# ECU_Adapter.net
KiCad netlist of a schematic drawn in EAGLE
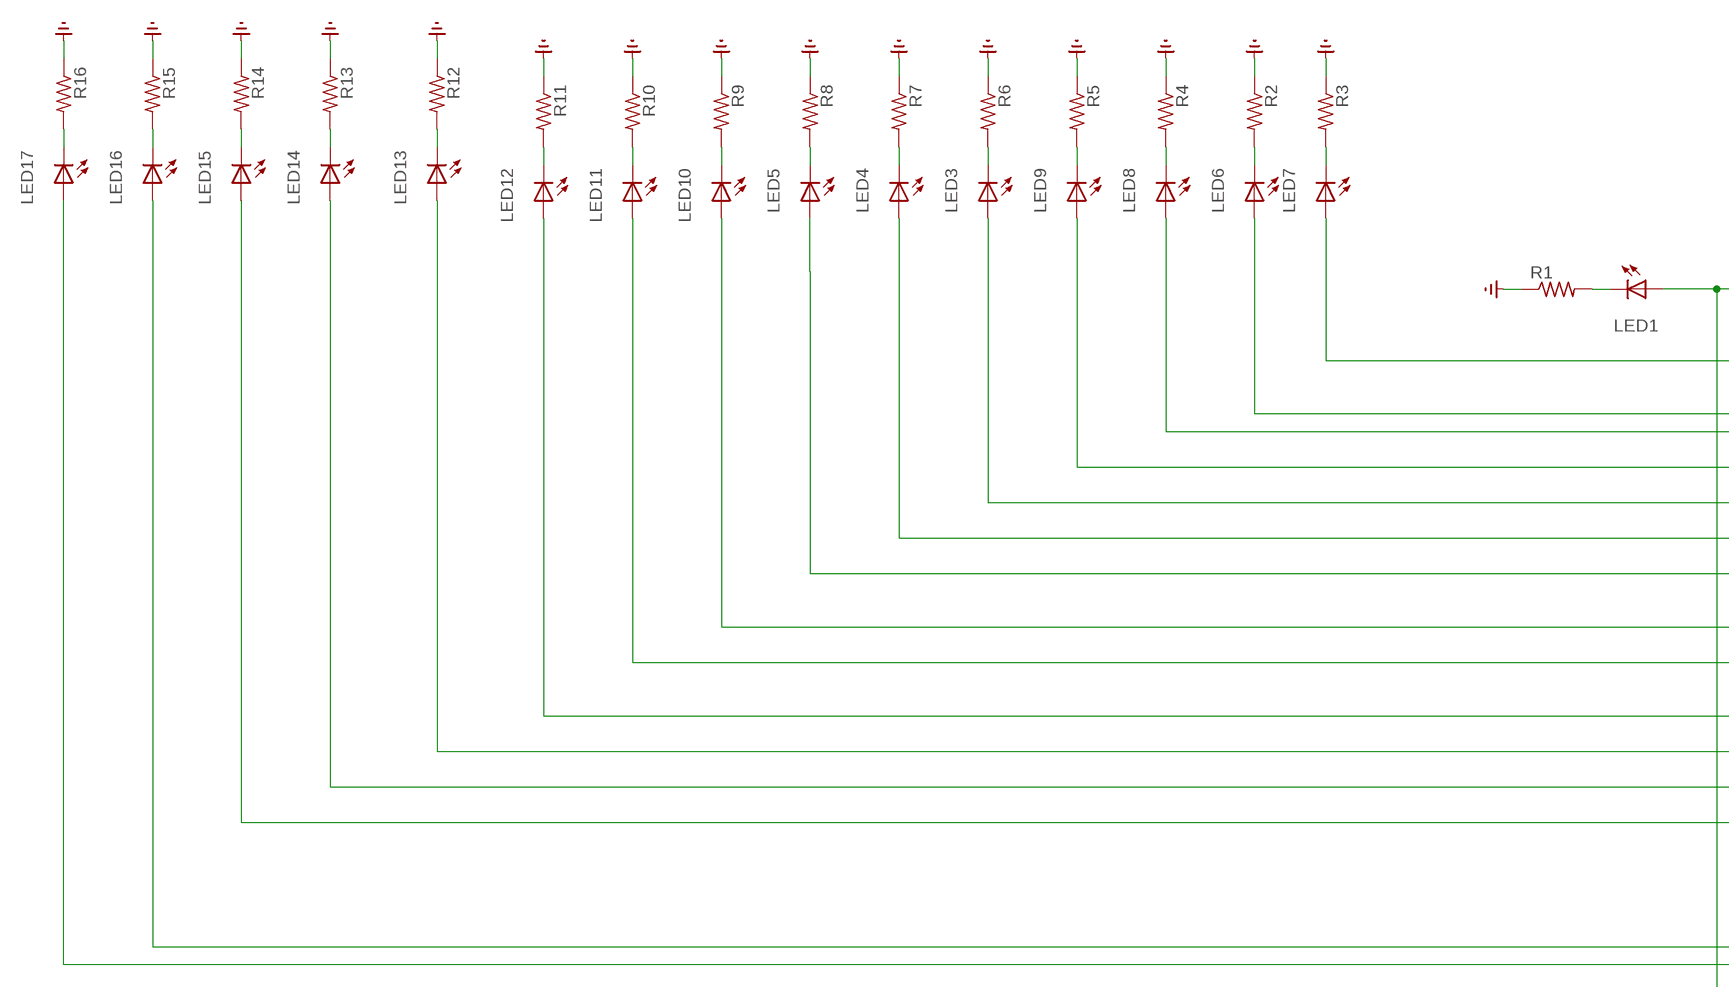
[diagram p0: schematic, sheet 1, part 1 of 2]
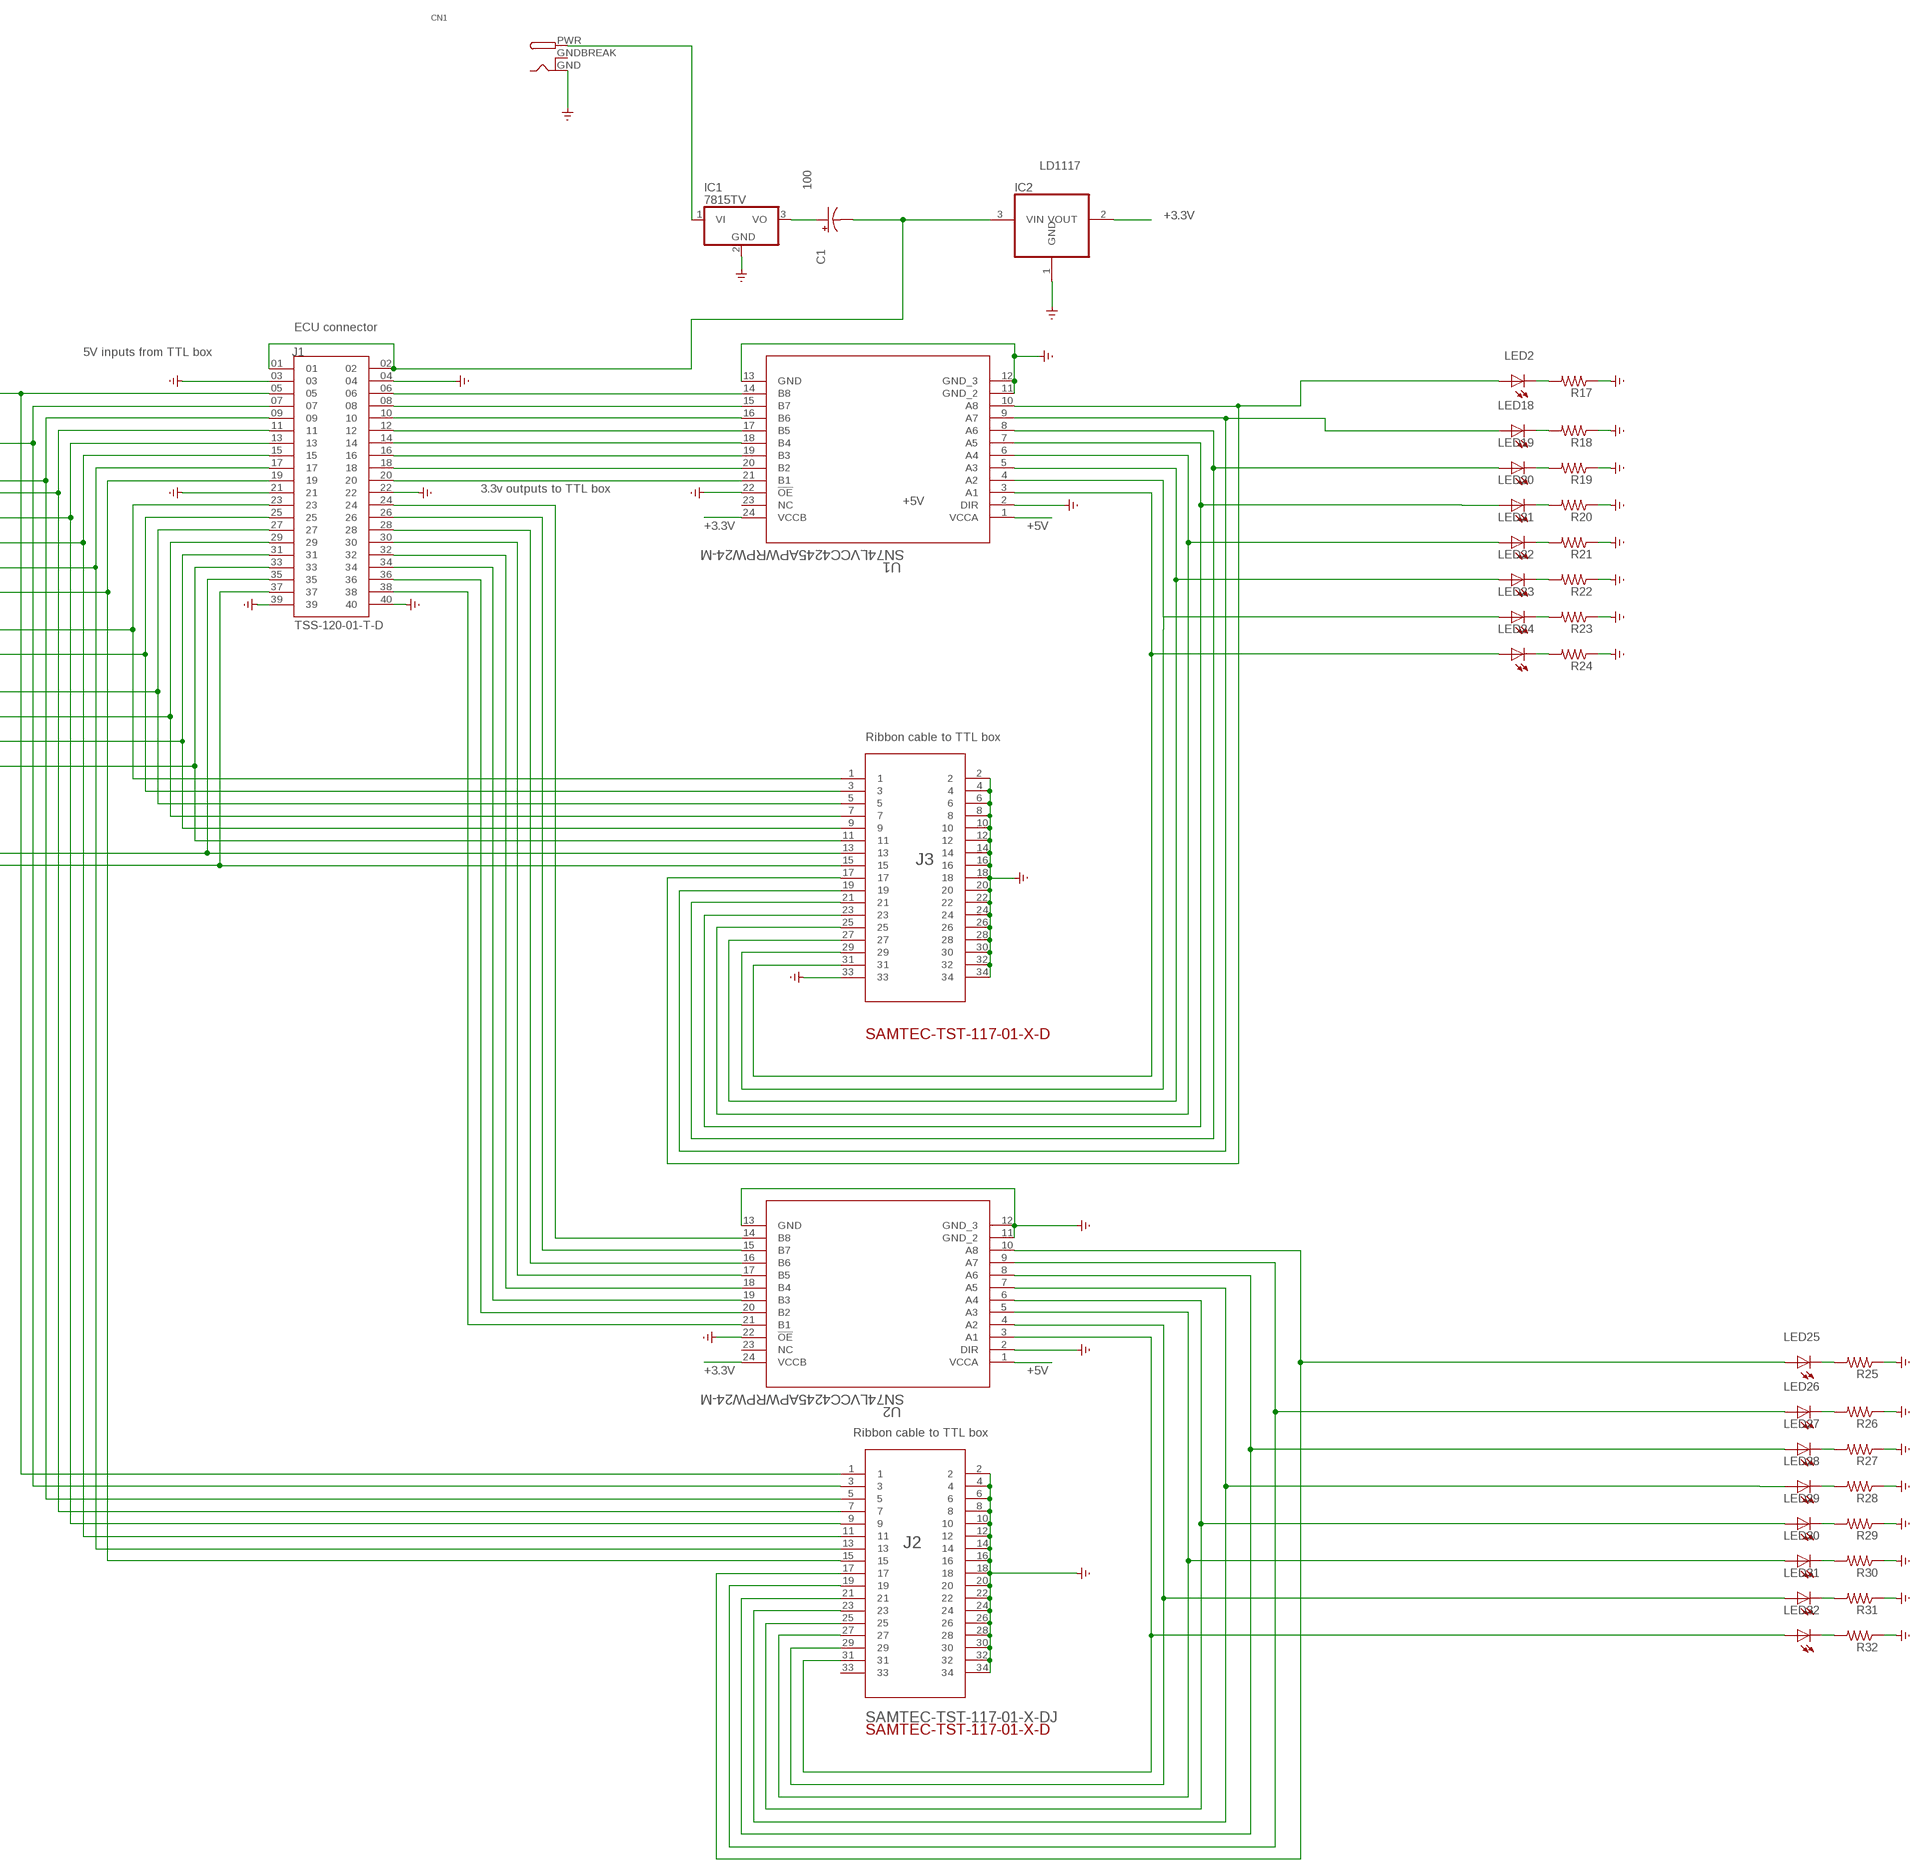
[diagram p1: schematic, sheet 1, part 2 of 2]

(export (version "E")
  (design (tool "Eeschema 10.0.6"))
  (components
    (comp (ref "C1")
      (value "100")
      (footprint "eagle-import:E3,5-10")
      (libsource (lib "eagle-import") (part "CPOL-USE3.5-10"))
    )
    (comp (ref "CN1")
      (value "DCBARRELPTH")
      (footprint "eagle-import:DCJACK_2MM_PTH")
      (libsource (lib "eagle-import") (part "DCBARRELPTH"))
    )
    (comp (ref "IC1")
      (value "7815TV")
      (footprint "eagle-import:TO220V")
      (libsource (lib "eagle-import") (part "78TV15"))
    )
    (comp (ref "IC2")
      (value "LD1117")
      (footprint "eagle-import:SOT223")
      (fields (field (name "MF") "TEXAS INSTRUMENTS") (field (name "MPN") "REG1117FAKTTT"))
      (libsource (lib "eagle-import") (part "LD1117"))
    )
    (comp (ref "J1")
      (value "TSS-120-01-T-D")
      (footprint "eagle-import:SAMTEC_TSS-120-01-T-D")
      (fields (field (name "MF") "Samtec"))
      (libsource (lib "eagle-import") (part "TSS-120-01-T-D"))
    )
    (comp (ref "J2")
      (value "SAMTEC-TST-117-01-X-DJ")
      (footprint "eagle-import:SAMTEC-TST-117-01-X-D")
      (fields
        (field (name "DIGI-KEY_PART_NUMBER") "TST-117-01-L-D-LL-ND")
        (field (name "MF") "Samtec Inc.")
        (field (name "MP") "TST-117-01-L-D")
      )
      (libsource (lib "eagle-import") (part "SAMTEC-TST-117-01-X-DJ"))
    )
    (comp (ref "J3")
      (value "SAMTEC-TST-117-01-X-DJ")
      (footprint "eagle-import:SAMTEC-TST-117-01-X-D")
      (fields
        (field (name "DIGI-KEY_PART_NUMBER") "TST-117-01-L-D-LL-ND")
        (field (name "MF") "Samtec Inc.")
        (field (name "MP") "TST-117-01-L-D")
      )
      (libsource (lib "eagle-import") (part "SAMTEC-TST-117-01-X-DJ"))
    )
    (comp (ref "LED1")
      (value "LEDCHIPLED_0603")
      (footprint "eagle-import:CHIPLED_0603")
      (libsource (lib "eagle-import") (part "LEDCHIPLED_0603"))
    )
    (comp (ref "LED2")
      (value "LEDCHIPLED_0603")
      (footprint "eagle-import:CHIPLED_0603")
      (libsource (lib "eagle-import") (part "LEDCHIPLED_0603"))
    )
    (comp (ref "LED3")
      (value "LEDCHIPLED_0603")
      (footprint "eagle-import:CHIPLED_0603")
      (libsource (lib "eagle-import") (part "LEDCHIPLED_0603"))
    )
    (comp (ref "LED4")
      (value "LEDCHIPLED_0603")
      (footprint "eagle-import:CHIPLED_0603")
      (libsource (lib "eagle-import") (part "LEDCHIPLED_0603"))
    )
    (comp (ref "LED5")
      (value "LEDCHIPLED_0603")
      (footprint "eagle-import:CHIPLED_0603")
      (libsource (lib "eagle-import") (part "LEDCHIPLED_0603"))
    )
    (comp (ref "LED6")
      (value "LEDCHIPLED_0603")
      (footprint "eagle-import:CHIPLED_0603")
      (libsource (lib "eagle-import") (part "LEDCHIPLED_0603"))
    )
    (comp (ref "LED7")
      (value "LEDCHIPLED_0603")
      (footprint "eagle-import:CHIPLED_0603")
      (libsource (lib "eagle-import") (part "LEDCHIPLED_0603"))
    )
    (comp (ref "LED8")
      (value "LEDCHIPLED_0603")
      (footprint "eagle-import:CHIPLED_0603")
      (libsource (lib "eagle-import") (part "LEDCHIPLED_0603"))
    )
    (comp (ref "LED9")
      (value "LEDCHIPLED_0603")
      (footprint "eagle-import:CHIPLED_0603")
      (libsource (lib "eagle-import") (part "LEDCHIPLED_0603"))
    )
    (comp (ref "LED10")
      (value "LEDCHIPLED_0603")
      (footprint "eagle-import:CHIPLED_0603")
      (libsource (lib "eagle-import") (part "LEDCHIPLED_0603"))
    )
    (comp (ref "LED11")
      (value "LEDCHIPLED_0603")
      (footprint "eagle-import:CHIPLED_0603")
      (libsource (lib "eagle-import") (part "LEDCHIPLED_0603"))
    )
    (comp (ref "LED12")
      (value "LEDCHIPLED_0603")
      (footprint "eagle-import:CHIPLED_0603")
      (libsource (lib "eagle-import") (part "LEDCHIPLED_0603"))
    )
    (comp (ref "LED13")
      (value "LEDCHIPLED_0603")
      (footprint "eagle-import:CHIPLED_0603")
      (libsource (lib "eagle-import") (part "LEDCHIPLED_0603"))
    )
    (comp (ref "LED14")
      (value "LEDCHIPLED_0603")
      (footprint "eagle-import:CHIPLED_0603")
      (libsource (lib "eagle-import") (part "LEDCHIPLED_0603"))
    )
    (comp (ref "LED15")
      (value "LEDCHIPLED_0603")
      (footprint "eagle-import:CHIPLED_0603")
      (libsource (lib "eagle-import") (part "LEDCHIPLED_0603"))
    )
    (comp (ref "LED16")
      (value "LEDCHIPLED_0603")
      (footprint "eagle-import:CHIPLED_0603")
      (libsource (lib "eagle-import") (part "LEDCHIPLED_0603"))
    )
    (comp (ref "LED17")
      (value "LEDCHIPLED_0603")
      (footprint "eagle-import:CHIPLED_0603")
      (libsource (lib "eagle-import") (part "LEDCHIPLED_0603"))
    )
    (comp (ref "LED18")
      (value "LEDCHIPLED_0603")
      (footprint "eagle-import:CHIPLED_0603")
      (libsource (lib "eagle-import") (part "LEDCHIPLED_0603"))
    )
    (comp (ref "LED19")
      (value "LEDCHIPLED_0603")
      (footprint "eagle-import:CHIPLED_0603")
      (libsource (lib "eagle-import") (part "LEDCHIPLED_0603"))
    )
    (comp (ref "LED20")
      (value "LEDCHIPLED_0603")
      (footprint "eagle-import:CHIPLED_0603")
      (libsource (lib "eagle-import") (part "LEDCHIPLED_0603"))
    )
    (comp (ref "LED21")
      (value "LEDCHIPLED_0603")
      (footprint "eagle-import:CHIPLED_0603")
      (libsource (lib "eagle-import") (part "LEDCHIPLED_0603"))
    )
    (comp (ref "LED22")
      (value "LEDCHIPLED_0603")
      (footprint "eagle-import:CHIPLED_0603")
      (libsource (lib "eagle-import") (part "LEDCHIPLED_0603"))
    )
    (comp (ref "LED23")
      (value "LEDCHIPLED_0603")
      (footprint "eagle-import:CHIPLED_0603")
      (libsource (lib "eagle-import") (part "LEDCHIPLED_0603"))
    )
    (comp (ref "LED24")
      (value "LEDCHIPLED_0603")
      (footprint "eagle-import:CHIPLED_0603")
      (libsource (lib "eagle-import") (part "LEDCHIPLED_0603"))
    )
    (comp (ref "LED25")
      (value "LEDCHIPLED_0603")
      (footprint "eagle-import:CHIPLED_0603")
      (libsource (lib "eagle-import") (part "LEDCHIPLED_0603"))
    )
    (comp (ref "LED26")
      (value "LEDCHIPLED_0603")
      (footprint "eagle-import:CHIPLED_0603")
      (libsource (lib "eagle-import") (part "LEDCHIPLED_0603"))
    )
    (comp (ref "LED27")
      (value "LEDCHIPLED_0603")
      (footprint "eagle-import:CHIPLED_0603")
      (libsource (lib "eagle-import") (part "LEDCHIPLED_0603"))
    )
    (comp (ref "LED28")
      (value "LEDCHIPLED_0603")
      (footprint "eagle-import:CHIPLED_0603")
      (libsource (lib "eagle-import") (part "LEDCHIPLED_0603"))
    )
    (comp (ref "LED29")
      (value "LEDCHIPLED_0603")
      (footprint "eagle-import:CHIPLED_0603")
      (libsource (lib "eagle-import") (part "LEDCHIPLED_0603"))
    )
    (comp (ref "LED30")
      (value "LEDCHIPLED_0603")
      (footprint "eagle-import:CHIPLED_0603")
      (libsource (lib "eagle-import") (part "LEDCHIPLED_0603"))
    )
    (comp (ref "LED31")
      (value "LEDCHIPLED_0603")
      (footprint "eagle-import:CHIPLED_0603")
      (libsource (lib "eagle-import") (part "LEDCHIPLED_0603"))
    )
    (comp (ref "LED32")
      (value "LEDCHIPLED_0603")
      (footprint "eagle-import:CHIPLED_0603")
      (libsource (lib "eagle-import") (part "LEDCHIPLED_0603"))
    )
    (comp (ref "R1")
      (value "R-US_R0603")
      (footprint "eagle-import:R0603")
      (libsource (lib "eagle-import") (part "R-US_R0603"))
    )
    (comp (ref "R2")
      (value "R-US_R0603")
      (footprint "eagle-import:R0603")
      (libsource (lib "eagle-import") (part "R-US_R0603"))
    )
    (comp (ref "R3")
      (value "R-US_R0603")
      (footprint "eagle-import:R0603")
      (libsource (lib "eagle-import") (part "R-US_R0603"))
    )
    (comp (ref "R4")
      (value "R-US_R0603")
      (footprint "eagle-import:R0603")
      (libsource (lib "eagle-import") (part "R-US_R0603"))
    )
    (comp (ref "R5")
      (value "R-US_R0603")
      (footprint "eagle-import:R0603")
      (libsource (lib "eagle-import") (part "R-US_R0603"))
    )
    (comp (ref "R6")
      (value "R-US_R0603")
      (footprint "eagle-import:R0603")
      (libsource (lib "eagle-import") (part "R-US_R0603"))
    )
    (comp (ref "R7")
      (value "R-US_R0603")
      (footprint "eagle-import:R0603")
      (libsource (lib "eagle-import") (part "R-US_R0603"))
    )
    (comp (ref "R8")
      (value "R-US_R0603")
      (footprint "eagle-import:R0603")
      (libsource (lib "eagle-import") (part "R-US_R0603"))
    )
    (comp (ref "R9")
      (value "R-US_R0603")
      (footprint "eagle-import:R0603")
      (libsource (lib "eagle-import") (part "R-US_R0603"))
    )
    (comp (ref "R10")
      (value "R-US_R0603")
      (footprint "eagle-import:R0603")
      (libsource (lib "eagle-import") (part "R-US_R0603"))
    )
    (comp (ref "R11")
      (value "R-US_R0603")
      (footprint "eagle-import:R0603")
      (libsource (lib "eagle-import") (part "R-US_R0603"))
    )
    (comp (ref "R12")
      (value "R-US_R0603")
      (footprint "eagle-import:R0603")
      (libsource (lib "eagle-import") (part "R-US_R0603"))
    )
    (comp (ref "R13")
      (value "R-US_R0603")
      (footprint "eagle-import:R0603")
      (libsource (lib "eagle-import") (part "R-US_R0603"))
    )
    (comp (ref "R14")
      (value "R-US_R0603")
      (footprint "eagle-import:R0603")
      (libsource (lib "eagle-import") (part "R-US_R0603"))
    )
    (comp (ref "R15")
      (value "R-US_R0603")
      (footprint "eagle-import:R0603")
      (libsource (lib "eagle-import") (part "R-US_R0603"))
    )
    (comp (ref "R16")
      (value "R-US_R0603")
      (footprint "eagle-import:R0603")
      (libsource (lib "eagle-import") (part "R-US_R0603"))
    )
    (comp (ref "R17")
      (value "R-US_R0603")
      (footprint "eagle-import:R0603")
      (libsource (lib "eagle-import") (part "R-US_R0603"))
    )
    (comp (ref "R18")
      (value "R-US_R0603")
      (footprint "eagle-import:R0603")
      (libsource (lib "eagle-import") (part "R-US_R0603"))
    )
    (comp (ref "R19")
      (value "R-US_R0603")
      (footprint "eagle-import:R0603")
      (libsource (lib "eagle-import") (part "R-US_R0603"))
    )
    (comp (ref "R20")
      (value "R-US_R0603")
      (footprint "eagle-import:R0603")
      (libsource (lib "eagle-import") (part "R-US_R0603"))
    )
    (comp (ref "R21")
      (value "R-US_R0603")
      (footprint "eagle-import:R0603")
      (libsource (lib "eagle-import") (part "R-US_R0603"))
    )
    (comp (ref "R22")
      (value "R-US_R0603")
      (footprint "eagle-import:R0603")
      (libsource (lib "eagle-import") (part "R-US_R0603"))
    )
    (comp (ref "R23")
      (value "R-US_R0603")
      (footprint "eagle-import:R0603")
      (libsource (lib "eagle-import") (part "R-US_R0603"))
    )
    (comp (ref "R24")
      (value "R-US_R0603")
      (footprint "eagle-import:R0603")
      (libsource (lib "eagle-import") (part "R-US_R0603"))
    )
    (comp (ref "R25")
      (value "R-US_R0603")
      (footprint "eagle-import:R0603")
      (libsource (lib "eagle-import") (part "R-US_R0603"))
    )
    (comp (ref "R26")
      (value "R-US_R0603")
      (footprint "eagle-import:R0603")
      (libsource (lib "eagle-import") (part "R-US_R0603"))
    )
    (comp (ref "R27")
      (value "R-US_R0603")
      (footprint "eagle-import:R0603")
      (libsource (lib "eagle-import") (part "R-US_R0603"))
    )
    (comp (ref "R28")
      (value "R-US_R0603")
      (footprint "eagle-import:R0603")
      (libsource (lib "eagle-import") (part "R-US_R0603"))
    )
    (comp (ref "R29")
      (value "R-US_R0603")
      (footprint "eagle-import:R0603")
      (libsource (lib "eagle-import") (part "R-US_R0603"))
    )
    (comp (ref "R30")
      (value "R-US_R0603")
      (footprint "eagle-import:R0603")
      (libsource (lib "eagle-import") (part "R-US_R0603"))
    )
    (comp (ref "R31")
      (value "R-US_R0603")
      (footprint "eagle-import:R0603")
      (libsource (lib "eagle-import") (part "R-US_R0603"))
    )
    (comp (ref "R32")
      (value "R-US_R0603")
      (footprint "eagle-import:R0603")
      (libsource (lib "eagle-import") (part "R-US_R0603"))
    )
    (comp (ref "U1")
      (value "SN74LVCC4245APWRPW24-M")
      (footprint "eagle-import:PW24-M")
      (fields
        (field (name "GENERIC_PART_NUMBER") "SN74LVCC4245A")
        (field (name "MANUFACTURER") "Texas Instruments")
        (field (name "MANUFACTURER_PART_NUMBER") "SN74LVCC4245APWR")
      )
      (libsource (lib "eagle-import") (part "SN74LVCC4245APWRPW24-M"))
    )
    (comp (ref "U2")
      (value "SN74LVCC4245APWRPW24-M")
      (footprint "eagle-import:PW24-M")
      (fields
        (field (name "GENERIC_PART_NUMBER") "SN74LVCC4245A")
        (field (name "MANUFACTURER") "Texas Instruments")
        (field (name "MANUFACTURER_PART_NUMBER") "SN74LVCC4245APWR")
      )
      (libsource (lib "eagle-import") (part "SN74LVCC4245APWRPW24-M"))
    )
  )
  (nets
    (net (code "1") (name "/+3.3V") (class "Default")
      (node (ref "IC2") (pin "2") (pinfunction "VOUT_2") (pintype "output"))
      (node (ref "U1") (pin "24") (pinfunction "VCCB_24") (pintype "power_in"))
      (node (ref "U2") (pin "24") (pinfunction "VCCB_24") (pintype "power_in"))
    )
    (net (code "2") (name "/+5V") (class "Default")
      (node (ref "C1") (pin "-") (pinfunction "-_-") (pintype "passive"))
      (node (ref "IC2") (pin "3") (pinfunction "VIN_3") (pintype "input"))
      (node (ref "J1") (pin "01") (pinfunction "01_01") (pintype "passive"))
      (node (ref "J1") (pin "02") (pinfunction "02_02") (pintype "passive"))
      (node (ref "U1") (pin "1") (pinfunction "VCCA_1") (pintype "power_in"))
      (node (ref "U2") (pin "1") (pinfunction "VCCA_1") (pintype "power_in"))
    )
    (net (code "3") (name "/GNDBREAK") (class "Default")
      (node (ref "CN1") (pin "GNDBREAK") (pinfunction "GNDBREAK_GNDBREAK") (pintype "power_in"))
    )
    (net (code "4") (name "Net-(IC1-VI)") (class "Default")
      (node (ref "CN1") (pin "PWR") (pinfunction "PWR_PWR") (pintype "power_in"))
      (node (ref "IC1") (pin "1") (pinfunction "VI_1") (pintype "input"))
    )
    (net (code "5") (name "Net-(IC1-VO)") (class "Default")
      (node (ref "C1") (pin "+") (pinfunction "+_+") (pintype "passive"))
      (node (ref "IC1") (pin "3") (pinfunction "VO_3") (pintype "passive"))
    )
    (net (code "6") (name "Net-(J1-Pad05)") (class "Default")
      (node (ref "J1") (pin "05") (pinfunction "05_05") (pintype "passive"))
      (node (ref "J2") (pin "1") (pinfunction "1_1") (pintype "passive"))
      (node (ref "LED1") (pin "A") (pinfunction "A_A") (pintype "passive"))
    )
    (net (code "7") (name "Net-(J1-Pad07)") (class "Default")
      (node (ref "J1") (pin "07") (pinfunction "07_07") (pintype "passive"))
      (node (ref "J2") (pin "3") (pinfunction "3_3") (pintype "passive"))
      (node (ref "LED7") (pin "A") (pinfunction "A_A") (pintype "passive"))
    )
    (net (code "8") (name "Net-(J1-Pad09)") (class "Default")
      (node (ref "J1") (pin "09") (pinfunction "09_09") (pintype "passive"))
      (node (ref "J2") (pin "5") (pinfunction "5_5") (pintype "passive"))
      (node (ref "LED6") (pin "A") (pinfunction "A_A") (pintype "passive"))
    )
    (net (code "9") (name "Net-(J1-Pad11)") (class "Default")
      (node (ref "J1") (pin "11") (pinfunction "11_11") (pintype "passive"))
      (node (ref "J2") (pin "7") (pinfunction "7_7") (pintype "passive"))
      (node (ref "LED8") (pin "A") (pinfunction "A_A") (pintype "passive"))
    )
    (net (code "10") (name "Net-(J1-Pad13)") (class "Default")
      (node (ref "J1") (pin "13") (pinfunction "13_13") (pintype "passive"))
      (node (ref "J2") (pin "9") (pinfunction "9_9") (pintype "passive"))
      (node (ref "LED9") (pin "A") (pinfunction "A_A") (pintype "passive"))
    )
    (net (code "11") (name "Net-(J1-Pad15)") (class "Default")
      (node (ref "J1") (pin "15") (pinfunction "15_15") (pintype "passive"))
      (node (ref "J2") (pin "11") (pinfunction "11_11") (pintype "passive"))
      (node (ref "LED3") (pin "A") (pinfunction "A_A") (pintype "passive"))
    )
    (net (code "12") (name "Net-(J1-Pad17)") (class "Default")
      (node (ref "J1") (pin "17") (pinfunction "17_17") (pintype "passive"))
      (node (ref "J2") (pin "13") (pinfunction "13_13") (pintype "passive"))
      (node (ref "LED4") (pin "A") (pinfunction "A_A") (pintype "passive"))
    )
    (net (code "13") (name "Net-(J1-Pad19)") (class "Default")
      (node (ref "J1") (pin "19") (pinfunction "19_19") (pintype "passive"))
      (node (ref "J2") (pin "15") (pinfunction "15_15") (pintype "passive"))
      (node (ref "LED5") (pin "A") (pinfunction "A_A") (pintype "passive"))
    )
    (net (code "14") (name "Net-(J1-Pad23)") (class "Default")
      (node (ref "J1") (pin "23") (pinfunction "23_23") (pintype "passive"))
      (node (ref "J3") (pin "1") (pinfunction "1_1") (pintype "passive"))
      (node (ref "LED10") (pin "A") (pinfunction "A_A") (pintype "passive"))
    )
    (net (code "15") (name "Net-(J1-Pad25)") (class "Default")
      (node (ref "J1") (pin "25") (pinfunction "25_25") (pintype "passive"))
      (node (ref "J3") (pin "3") (pinfunction "3_3") (pintype "passive"))
      (node (ref "LED11") (pin "A") (pinfunction "A_A") (pintype "passive"))
    )
    (net (code "16") (name "Net-(J1-Pad27)") (class "Default")
      (node (ref "J1") (pin "27") (pinfunction "27_27") (pintype "passive"))
      (node (ref "J3") (pin "5") (pinfunction "5_5") (pintype "passive"))
      (node (ref "LED12") (pin "A") (pinfunction "A_A") (pintype "passive"))
    )
    (net (code "17") (name "Net-(J1-Pad29)") (class "Default")
      (node (ref "J1") (pin "29") (pinfunction "29_29") (pintype "passive"))
      (node (ref "J3") (pin "7") (pinfunction "7_7") (pintype "passive"))
      (node (ref "LED13") (pin "A") (pinfunction "A_A") (pintype "passive"))
    )
    (net (code "18") (name "Net-(J1-Pad31)") (class "Default")
      (node (ref "J1") (pin "31") (pinfunction "31_31") (pintype "passive"))
      (node (ref "J3") (pin "9") (pinfunction "9_9") (pintype "passive"))
      (node (ref "LED14") (pin "A") (pinfunction "A_A") (pintype "passive"))
    )
    (net (code "19") (name "Net-(J1-Pad33)") (class "Default")
      (node (ref "J1") (pin "33") (pinfunction "33_33") (pintype "passive"))
      (node (ref "J3") (pin "11") (pinfunction "11_11") (pintype "passive"))
      (node (ref "LED15") (pin "A") (pinfunction "A_A") (pintype "passive"))
    )
    (net (code "20") (name "Net-(J1-Pad35)") (class "Default")
      (node (ref "J1") (pin "35") (pinfunction "35_35") (pintype "passive"))
      (node (ref "J3") (pin "13") (pinfunction "13_13") (pintype "passive"))
      (node (ref "LED16") (pin "A") (pinfunction "A_A") (pintype "passive"))
    )
    (net (code "21") (name "Net-(J1-Pad37)") (class "Default")
      (node (ref "J1") (pin "37") (pinfunction "37_37") (pintype "passive"))
      (node (ref "J3") (pin "15") (pinfunction "15_15") (pintype "passive"))
      (node (ref "LED17") (pin "A") (pinfunction "A_A") (pintype "passive"))
    )
    (net (code "22") (name "Net-(LED1-PadC)") (class "Default")
      (node (ref "LED1") (pin "C") (pinfunction "C_C") (pintype "passive"))
      (node (ref "R1") (pin "2") (pinfunction "2_2") (pintype "passive"))
    )
    (net (code "23") (name "Net-(LED2-PadC)") (class "Default")
      (node (ref "LED2") (pin "C") (pinfunction "C_C") (pintype "passive"))
      (node (ref "R17") (pin "2") (pinfunction "2_2") (pintype "passive"))
    )
    (net (code "24") (name "Net-(LED3-PadC)") (class "Default")
      (node (ref "LED3") (pin "C") (pinfunction "C_C") (pintype "passive"))
      (node (ref "R6") (pin "2") (pinfunction "2_2") (pintype "passive"))
    )
    (net (code "25") (name "Net-(LED4-PadC)") (class "Default")
      (node (ref "LED4") (pin "C") (pinfunction "C_C") (pintype "passive"))
      (node (ref "R7") (pin "2") (pinfunction "2_2") (pintype "passive"))
    )
    (net (code "26") (name "Net-(LED5-PadC)") (class "Default")
      (node (ref "LED5") (pin "C") (pinfunction "C_C") (pintype "passive"))
      (node (ref "R8") (pin "2") (pinfunction "2_2") (pintype "passive"))
    )
    (net (code "27") (name "Net-(LED6-PadC)") (class "Default")
      (node (ref "LED6") (pin "C") (pinfunction "C_C") (pintype "passive"))
      (node (ref "R2") (pin "2") (pinfunction "2_2") (pintype "passive"))
    )
    (net (code "28") (name "Net-(LED7-PadC)") (class "Default")
      (node (ref "LED7") (pin "C") (pinfunction "C_C") (pintype "passive"))
      (node (ref "R3") (pin "2") (pinfunction "2_2") (pintype "passive"))
    )
    (net (code "29") (name "Net-(LED8-PadC)") (class "Default")
      (node (ref "LED8") (pin "C") (pinfunction "C_C") (pintype "passive"))
      (node (ref "R4") (pin "2") (pinfunction "2_2") (pintype "passive"))
    )
    (net (code "30") (name "Net-(LED9-PadC)") (class "Default")
      (node (ref "LED9") (pin "C") (pinfunction "C_C") (pintype "passive"))
      (node (ref "R5") (pin "2") (pinfunction "2_2") (pintype "passive"))
    )
    (net (code "31") (name "Net-(LED10-PadC)") (class "Default")
      (node (ref "LED10") (pin "C") (pinfunction "C_C") (pintype "passive"))
      (node (ref "R9") (pin "2") (pinfunction "2_2") (pintype "passive"))
    )
    (net (code "32") (name "Net-(LED11-PadC)") (class "Default")
      (node (ref "LED11") (pin "C") (pinfunction "C_C") (pintype "passive"))
      (node (ref "R10") (pin "2") (pinfunction "2_2") (pintype "passive"))
    )
    (net (code "33") (name "Net-(LED12-PadC)") (class "Default")
      (node (ref "LED12") (pin "C") (pinfunction "C_C") (pintype "passive"))
      (node (ref "R11") (pin "2") (pinfunction "2_2") (pintype "passive"))
    )
    (net (code "34") (name "Net-(LED13-PadC)") (class "Default")
      (node (ref "LED13") (pin "C") (pinfunction "C_C") (pintype "passive"))
      (node (ref "R12") (pin "2") (pinfunction "2_2") (pintype "passive"))
    )
    (net (code "35") (name "Net-(LED14-PadC)") (class "Default")
      (node (ref "LED14") (pin "C") (pinfunction "C_C") (pintype "passive"))
      (node (ref "R13") (pin "2") (pinfunction "2_2") (pintype "passive"))
    )
    (net (code "36") (name "Net-(LED15-PadC)") (class "Default")
      (node (ref "LED15") (pin "C") (pinfunction "C_C") (pintype "passive"))
      (node (ref "R14") (pin "2") (pinfunction "2_2") (pintype "passive"))
    )
    (net (code "37") (name "Net-(LED16-PadC)") (class "Default")
      (node (ref "LED16") (pin "C") (pinfunction "C_C") (pintype "passive"))
      (node (ref "R15") (pin "2") (pinfunction "2_2") (pintype "passive"))
    )
    (net (code "38") (name "Net-(LED17-PadC)") (class "Default")
      (node (ref "LED17") (pin "C") (pinfunction "C_C") (pintype "passive"))
      (node (ref "R16") (pin "2") (pinfunction "2_2") (pintype "passive"))
    )
    (net (code "39") (name "Net-(LED18-PadC)") (class "Default")
      (node (ref "LED18") (pin "C") (pinfunction "C_C") (pintype "passive"))
      (node (ref "R18") (pin "2") (pinfunction "2_2") (pintype "passive"))
    )
    (net (code "40") (name "Net-(LED19-PadC)") (class "Default")
      (node (ref "LED19") (pin "C") (pinfunction "C_C") (pintype "passive"))
      (node (ref "R19") (pin "2") (pinfunction "2_2") (pintype "passive"))
    )
    (net (code "41") (name "Net-(LED20-PadC)") (class "Default")
      (node (ref "LED20") (pin "C") (pinfunction "C_C") (pintype "passive"))
      (node (ref "R20") (pin "2") (pinfunction "2_2") (pintype "passive"))
    )
    (net (code "42") (name "Net-(LED21-PadC)") (class "Default")
      (node (ref "LED21") (pin "C") (pinfunction "C_C") (pintype "passive"))
      (node (ref "R21") (pin "2") (pinfunction "2_2") (pintype "passive"))
    )
    (net (code "43") (name "Net-(LED22-PadC)") (class "Default")
      (node (ref "LED22") (pin "C") (pinfunction "C_C") (pintype "passive"))
      (node (ref "R22") (pin "2") (pinfunction "2_2") (pintype "passive"))
    )
    (net (code "44") (name "Net-(LED23-PadC)") (class "Default")
      (node (ref "LED23") (pin "C") (pinfunction "C_C") (pintype "passive"))
      (node (ref "R23") (pin "2") (pinfunction "2_2") (pintype "passive"))
    )
    (net (code "45") (name "Net-(LED24-PadC)") (class "Default")
      (node (ref "LED24") (pin "C") (pinfunction "C_C") (pintype "passive"))
      (node (ref "R24") (pin "2") (pinfunction "2_2") (pintype "passive"))
    )
    (net (code "46") (name "Net-(LED25-PadC)") (class "Default")
      (node (ref "LED25") (pin "C") (pinfunction "C_C") (pintype "passive"))
      (node (ref "R25") (pin "2") (pinfunction "2_2") (pintype "passive"))
    )
    (net (code "47") (name "Net-(LED26-PadC)") (class "Default")
      (node (ref "LED26") (pin "C") (pinfunction "C_C") (pintype "passive"))
      (node (ref "R26") (pin "2") (pinfunction "2_2") (pintype "passive"))
    )
    (net (code "48") (name "Net-(LED27-PadC)") (class "Default")
      (node (ref "LED27") (pin "C") (pinfunction "C_C") (pintype "passive"))
      (node (ref "R27") (pin "2") (pinfunction "2_2") (pintype "passive"))
    )
    (net (code "49") (name "Net-(LED28-PadC)") (class "Default")
      (node (ref "LED28") (pin "C") (pinfunction "C_C") (pintype "passive"))
      (node (ref "R28") (pin "2") (pinfunction "2_2") (pintype "passive"))
    )
    (net (code "50") (name "Net-(LED29-PadC)") (class "Default")
      (node (ref "LED29") (pin "C") (pinfunction "C_C") (pintype "passive"))
      (node (ref "R29") (pin "2") (pinfunction "2_2") (pintype "passive"))
    )
    (net (code "51") (name "Net-(LED30-PadC)") (class "Default")
      (node (ref "LED30") (pin "C") (pinfunction "C_C") (pintype "passive"))
      (node (ref "R30") (pin "2") (pinfunction "2_2") (pintype "passive"))
    )
    (net (code "52") (name "Net-(LED31-PadC)") (class "Default")
      (node (ref "LED31") (pin "C") (pinfunction "C_C") (pintype "passive"))
      (node (ref "R31") (pin "2") (pinfunction "2_2") (pintype "passive"))
    )
    (net (code "53") (name "Net-(LED32-PadC)") (class "Default")
      (node (ref "LED32") (pin "C") (pinfunction "C_C") (pintype "passive"))
      (node (ref "R32") (pin "2") (pinfunction "2_2") (pintype "passive"))
    )
    (net (code "54") (name "Net-(U1-A1)") (class "Default")
      (node (ref "J3") (pin "31") (pinfunction "31_31") (pintype "passive"))
      (node (ref "LED24") (pin "A") (pinfunction "A_A") (pintype "passive"))
      (node (ref "U1") (pin "3") (pinfunction "A1_3") (pintype "bidirectional"))
    )
    (net (code "55") (name "Net-(U1-A2)") (class "Default")
      (node (ref "J3") (pin "29") (pinfunction "29_29") (pintype "passive"))
      (node (ref "LED23") (pin "A") (pinfunction "A_A") (pintype "passive"))
      (node (ref "U1") (pin "4") (pinfunction "A2_4") (pintype "bidirectional"))
    )
    (net (code "56") (name "Net-(U1-A3)") (class "Default")
      (node (ref "J3") (pin "27") (pinfunction "27_27") (pintype "passive"))
      (node (ref "LED22") (pin "A") (pinfunction "A_A") (pintype "passive"))
      (node (ref "U1") (pin "5") (pinfunction "A3_5") (pintype "bidirectional"))
    )
    (net (code "57") (name "Net-(U1-A4)") (class "Default")
      (node (ref "J3") (pin "25") (pinfunction "25_25") (pintype "passive"))
      (node (ref "LED21") (pin "A") (pinfunction "A_A") (pintype "passive"))
      (node (ref "U1") (pin "6") (pinfunction "A4_6") (pintype "bidirectional"))
    )
    (net (code "58") (name "Net-(U1-A5)") (class "Default")
      (node (ref "J3") (pin "23") (pinfunction "23_23") (pintype "passive"))
      (node (ref "LED20") (pin "A") (pinfunction "A_A") (pintype "passive"))
      (node (ref "U1") (pin "7") (pinfunction "A5_7") (pintype "bidirectional"))
    )
    (net (code "59") (name "Net-(U1-A6)") (class "Default")
      (node (ref "J3") (pin "21") (pinfunction "21_21") (pintype "passive"))
      (node (ref "LED19") (pin "A") (pinfunction "A_A") (pintype "passive"))
      (node (ref "U1") (pin "8") (pinfunction "A6_8") (pintype "bidirectional"))
    )
    (net (code "60") (name "Net-(U1-A7)") (class "Default")
      (node (ref "J3") (pin "19") (pinfunction "19_19") (pintype "passive"))
      (node (ref "LED18") (pin "A") (pinfunction "A_A") (pintype "passive"))
      (node (ref "U1") (pin "9") (pinfunction "A7_9") (pintype "bidirectional"))
    )
    (net (code "61") (name "Net-(U1-A8)") (class "Default")
      (node (ref "J3") (pin "17") (pinfunction "17_17") (pintype "passive"))
      (node (ref "LED2") (pin "A") (pinfunction "A_A") (pintype "passive"))
      (node (ref "U1") (pin "10") (pinfunction "A8_10") (pintype "bidirectional"))
    )
    (net (code "62") (name "Net-(U1-B1)") (class "Default")
      (node (ref "J1") (pin "20") (pinfunction "20_20") (pintype "passive"))
      (node (ref "U1") (pin "21") (pinfunction "B1_21") (pintype "bidirectional"))
    )
    (net (code "63") (name "Net-(U1-B2)") (class "Default")
      (node (ref "J1") (pin "18") (pinfunction "18_18") (pintype "passive"))
      (node (ref "U1") (pin "20") (pinfunction "B2_20") (pintype "bidirectional"))
    )
    (net (code "64") (name "Net-(U1-B3)") (class "Default")
      (node (ref "J1") (pin "16") (pinfunction "16_16") (pintype "passive"))
      (node (ref "U1") (pin "19") (pinfunction "B3_19") (pintype "bidirectional"))
    )
    (net (code "65") (name "Net-(U1-B4)") (class "Default")
      (node (ref "J1") (pin "14") (pinfunction "14_14") (pintype "passive"))
      (node (ref "U1") (pin "18") (pinfunction "B4_18") (pintype "bidirectional"))
    )
    (net (code "66") (name "Net-(U1-B5)") (class "Default")
      (node (ref "J1") (pin "12") (pinfunction "12_12") (pintype "passive"))
      (node (ref "U1") (pin "17") (pinfunction "B5_17") (pintype "bidirectional"))
    )
    (net (code "67") (name "Net-(U1-B6)") (class "Default")
      (node (ref "J1") (pin "10") (pinfunction "10_10") (pintype "passive"))
      (node (ref "U1") (pin "16") (pinfunction "B6_16") (pintype "bidirectional"))
    )
    (net (code "68") (name "Net-(U1-B7)") (class "Default")
      (node (ref "J1") (pin "08") (pinfunction "08_08") (pintype "passive"))
      (node (ref "U1") (pin "15") (pinfunction "B7_15") (pintype "bidirectional"))
    )
    (net (code "69") (name "Net-(U1-B8)") (class "Default")
      (node (ref "J1") (pin "06") (pinfunction "06_06") (pintype "passive"))
      (node (ref "U1") (pin "14") (pinfunction "B8_14") (pintype "bidirectional"))
    )
    (net (code "70") (name "Net-(U2-A1)") (class "Default")
      (node (ref "J2") (pin "31") (pinfunction "31_31") (pintype "passive"))
      (node (ref "LED32") (pin "A") (pinfunction "A_A") (pintype "passive"))
      (node (ref "U2") (pin "3") (pinfunction "A1_3") (pintype "bidirectional"))
    )
    (net (code "71") (name "Net-(U2-A2)") (class "Default")
      (node (ref "J2") (pin "29") (pinfunction "29_29") (pintype "passive"))
      (node (ref "LED31") (pin "A") (pinfunction "A_A") (pintype "passive"))
      (node (ref "U2") (pin "4") (pinfunction "A2_4") (pintype "bidirectional"))
    )
    (net (code "72") (name "Net-(U2-A3)") (class "Default")
      (node (ref "J2") (pin "27") (pinfunction "27_27") (pintype "passive"))
      (node (ref "LED30") (pin "A") (pinfunction "A_A") (pintype "passive"))
      (node (ref "U2") (pin "5") (pinfunction "A3_5") (pintype "bidirectional"))
    )
    (net (code "73") (name "Net-(U2-A4)") (class "Default")
      (node (ref "J2") (pin "25") (pinfunction "25_25") (pintype "passive"))
      (node (ref "LED29") (pin "A") (pinfunction "A_A") (pintype "passive"))
      (node (ref "U2") (pin "6") (pinfunction "A4_6") (pintype "bidirectional"))
    )
    (net (code "74") (name "Net-(U2-A5)") (class "Default")
      (node (ref "J2") (pin "23") (pinfunction "23_23") (pintype "passive"))
      (node (ref "LED28") (pin "A") (pinfunction "A_A") (pintype "passive"))
      (node (ref "U2") (pin "7") (pinfunction "A5_7") (pintype "bidirectional"))
    )
    (net (code "75") (name "Net-(U2-A6)") (class "Default")
      (node (ref "J2") (pin "21") (pinfunction "21_21") (pintype "passive"))
      (node (ref "LED27") (pin "A") (pinfunction "A_A") (pintype "passive"))
      (node (ref "U2") (pin "8") (pinfunction "A6_8") (pintype "bidirectional"))
    )
    (net (code "76") (name "Net-(U2-A7)") (class "Default")
      (node (ref "J2") (pin "19") (pinfunction "19_19") (pintype "passive"))
      (node (ref "LED26") (pin "A") (pinfunction "A_A") (pintype "passive"))
      (node (ref "U2") (pin "9") (pinfunction "A7_9") (pintype "bidirectional"))
    )
    (net (code "77") (name "Net-(U2-A8)") (class "Default")
      (node (ref "J2") (pin "17") (pinfunction "17_17") (pintype "passive"))
      (node (ref "LED25") (pin "A") (pinfunction "A_A") (pintype "passive"))
      (node (ref "U2") (pin "10") (pinfunction "A8_10") (pintype "bidirectional"))
    )
    (net (code "78") (name "Net-(U2-B1)") (class "Default")
      (node (ref "J1") (pin "38") (pinfunction "38_38") (pintype "passive"))
      (node (ref "U2") (pin "21") (pinfunction "B1_21") (pintype "bidirectional"))
    )
    (net (code "79") (name "Net-(U2-B2)") (class "Default")
      (node (ref "J1") (pin "36") (pinfunction "36_36") (pintype "passive"))
      (node (ref "U2") (pin "20") (pinfunction "B2_20") (pintype "bidirectional"))
    )
    (net (code "80") (name "Net-(U2-B3)") (class "Default")
      (node (ref "J1") (pin "34") (pinfunction "34_34") (pintype "passive"))
      (node (ref "U2") (pin "19") (pinfunction "B3_19") (pintype "bidirectional"))
    )
    (net (code "81") (name "Net-(U2-B4)") (class "Default")
      (node (ref "J1") (pin "32") (pinfunction "32_32") (pintype "passive"))
      (node (ref "U2") (pin "18") (pinfunction "B4_18") (pintype "bidirectional"))
    )
    (net (code "82") (name "Net-(U2-B5)") (class "Default")
      (node (ref "J1") (pin "30") (pinfunction "30_30") (pintype "passive"))
      (node (ref "U2") (pin "17") (pinfunction "B5_17") (pintype "bidirectional"))
    )
    (net (code "83") (name "Net-(U2-B6)") (class "Default")
      (node (ref "J1") (pin "28") (pinfunction "28_28") (pintype "passive"))
      (node (ref "U2") (pin "16") (pinfunction "B6_16") (pintype "bidirectional"))
    )
    (net (code "84") (name "Net-(U2-B7)") (class "Default")
      (node (ref "J1") (pin "26") (pinfunction "26_26") (pintype "passive"))
      (node (ref "U2") (pin "15") (pinfunction "B7_15") (pintype "bidirectional"))
    )
    (net (code "85") (name "Net-(U2-B8)") (class "Default")
      (node (ref "J1") (pin "24") (pinfunction "24_24") (pintype "passive"))
      (node (ref "U2") (pin "14") (pinfunction "B8_14") (pintype "bidirectional"))
    )
    (net (code "86") (name "SUPPLY0_GND_") (class "Default")
      (node (ref "CN1") (pin "GND") (pinfunction "GND_GND") (pintype "power_in"))
      (node (ref "IC1") (pin "2") (pinfunction "GND_2") (pintype "passive"))
      (node (ref "IC2") (pin "1") (pinfunction "GND_1") (pintype "power_in"))
      (node (ref "J1") (pin "03") (pinfunction "03_03") (pintype "passive"))
      (node (ref "J1") (pin "04") (pinfunction "04_04") (pintype "passive"))
      (node (ref "J1") (pin "21") (pinfunction "21_21") (pintype "passive"))
      (node (ref "J1") (pin "22") (pinfunction "22_22") (pintype "passive"))
      (node (ref "J1") (pin "39") (pinfunction "39_39") (pintype "passive"))
      (node (ref "J1") (pin "40") (pinfunction "40_40") (pintype "passive"))
      (node (ref "J2") (pin "10") (pinfunction "10_10") (pintype "passive"))
      (node (ref "J2") (pin "12") (pinfunction "12_12") (pintype "passive"))
      (node (ref "J2") (pin "14") (pinfunction "14_14") (pintype "passive"))
      (node (ref "J2") (pin "16") (pinfunction "16_16") (pintype "passive"))
      (node (ref "J2") (pin "18") (pinfunction "18_18") (pintype "passive"))
      (node (ref "J2") (pin "2") (pinfunction "2_2") (pintype "passive"))
      (node (ref "J2") (pin "20") (pinfunction "20_20") (pintype "passive"))
      (node (ref "J2") (pin "22") (pinfunction "22_22") (pintype "passive"))
      (node (ref "J2") (pin "24") (pinfunction "24_24") (pintype "passive"))
      (node (ref "J2") (pin "26") (pinfunction "26_26") (pintype "passive"))
      (node (ref "J2") (pin "28") (pinfunction "28_28") (pintype "passive"))
      (node (ref "J2") (pin "30") (pinfunction "30_30") (pintype "passive"))
      (node (ref "J2") (pin "32") (pinfunction "32_32") (pintype "passive"))
      (node (ref "J2") (pin "34") (pinfunction "34_34") (pintype "passive"))
      (node (ref "J2") (pin "4") (pinfunction "4_4") (pintype "passive"))
      (node (ref "J2") (pin "6") (pinfunction "6_6") (pintype "passive"))
      (node (ref "J2") (pin "8") (pinfunction "8_8") (pintype "passive"))
      (node (ref "J3") (pin "10") (pinfunction "10_10") (pintype "passive"))
      (node (ref "J3") (pin "12") (pinfunction "12_12") (pintype "passive"))
      (node (ref "J3") (pin "14") (pinfunction "14_14") (pintype "passive"))
      (node (ref "J3") (pin "16") (pinfunction "16_16") (pintype "passive"))
      (node (ref "J3") (pin "18") (pinfunction "18_18") (pintype "passive"))
      (node (ref "J3") (pin "2") (pinfunction "2_2") (pintype "passive"))
      (node (ref "J3") (pin "20") (pinfunction "20_20") (pintype "passive"))
      (node (ref "J3") (pin "22") (pinfunction "22_22") (pintype "passive"))
      (node (ref "J3") (pin "24") (pinfunction "24_24") (pintype "passive"))
      (node (ref "J3") (pin "26") (pinfunction "26_26") (pintype "passive"))
      (node (ref "J3") (pin "28") (pinfunction "28_28") (pintype "passive"))
      (node (ref "J3") (pin "30") (pinfunction "30_30") (pintype "passive"))
      (node (ref "J3") (pin "32") (pinfunction "32_32") (pintype "passive"))
      (node (ref "J3") (pin "33") (pinfunction "33_33") (pintype "passive"))
      (node (ref "J3") (pin "34") (pinfunction "34_34") (pintype "passive"))
      (node (ref "J3") (pin "4") (pinfunction "4_4") (pintype "passive"))
      (node (ref "J3") (pin "6") (pinfunction "6_6") (pintype "passive"))
      (node (ref "J3") (pin "8") (pinfunction "8_8") (pintype "passive"))
      (node (ref "R1") (pin "1") (pinfunction "1_1") (pintype "passive"))
      (node (ref "R10") (pin "1") (pinfunction "1_1") (pintype "passive"))
      (node (ref "R11") (pin "1") (pinfunction "1_1") (pintype "passive"))
      (node (ref "R12") (pin "1") (pinfunction "1_1") (pintype "passive"))
      (node (ref "R13") (pin "1") (pinfunction "1_1") (pintype "passive"))
      (node (ref "R14") (pin "1") (pinfunction "1_1") (pintype "passive"))
      (node (ref "R15") (pin "1") (pinfunction "1_1") (pintype "passive"))
      (node (ref "R16") (pin "1") (pinfunction "1_1") (pintype "passive"))
      (node (ref "R17") (pin "1") (pinfunction "1_1") (pintype "passive"))
      (node (ref "R18") (pin "1") (pinfunction "1_1") (pintype "passive"))
      (node (ref "R19") (pin "1") (pinfunction "1_1") (pintype "passive"))
      (node (ref "R2") (pin "1") (pinfunction "1_1") (pintype "passive"))
      (node (ref "R20") (pin "1") (pinfunction "1_1") (pintype "passive"))
      (node (ref "R21") (pin "1") (pinfunction "1_1") (pintype "passive"))
      (node (ref "R22") (pin "1") (pinfunction "1_1") (pintype "passive"))
      (node (ref "R23") (pin "1") (pinfunction "1_1") (pintype "passive"))
      (node (ref "R24") (pin "1") (pinfunction "1_1") (pintype "passive"))
      (node (ref "R25") (pin "1") (pinfunction "1_1") (pintype "passive"))
      (node (ref "R26") (pin "1") (pinfunction "1_1") (pintype "passive"))
      (node (ref "R27") (pin "1") (pinfunction "1_1") (pintype "passive"))
      (node (ref "R28") (pin "1") (pinfunction "1_1") (pintype "passive"))
      (node (ref "R29") (pin "1") (pinfunction "1_1") (pintype "passive"))
      (node (ref "R3") (pin "1") (pinfunction "1_1") (pintype "passive"))
      (node (ref "R30") (pin "1") (pinfunction "1_1") (pintype "passive"))
      (node (ref "R31") (pin "1") (pinfunction "1_1") (pintype "passive"))
      (node (ref "R32") (pin "1") (pinfunction "1_1") (pintype "passive"))
      (node (ref "R4") (pin "1") (pinfunction "1_1") (pintype "passive"))
      (node (ref "R5") (pin "1") (pinfunction "1_1") (pintype "passive"))
      (node (ref "R6") (pin "1") (pinfunction "1_1") (pintype "passive"))
      (node (ref "R7") (pin "1") (pinfunction "1_1") (pintype "passive"))
      (node (ref "R8") (pin "1") (pinfunction "1_1") (pintype "passive"))
      (node (ref "R9") (pin "1") (pinfunction "1_1") (pintype "passive"))
      (node (ref "U1") (pin "11") (pinfunction "GND_2_11") (pintype "power_in"))
      (node (ref "U1") (pin "12") (pinfunction "GND_3_12") (pintype "power_in"))
      (node (ref "U1") (pin "13") (pinfunction "GND_13") (pintype "power_in"))
      (node (ref "U1") (pin "2") (pinfunction "DIR_2") (pintype "input"))
      (node (ref "U1") (pin "22") (pinfunction "~{OE}_22") (pintype "input"))
      (node (ref "U2") (pin "11") (pinfunction "GND_2_11") (pintype "power_in"))
      (node (ref "U2") (pin "12") (pinfunction "GND_3_12") (pintype "power_in"))
      (node (ref "U2") (pin "13") (pinfunction "GND_13") (pintype "power_in"))
      (node (ref "U2") (pin "2") (pinfunction "DIR_2") (pintype "input"))
      (node (ref "U2") (pin "22") (pinfunction "~{OE}_22") (pintype "input"))
    )
    (net (code "87") (name "unconnected-(J2-Pad33)") (class "Default")
      (node (ref "J2") (pin "33") (pinfunction "33_33") (pintype "passive"))
    )
    (net (code "88") (name "unconnected-(U1-NC-Pad23)") (class "Default")
      (node (ref "U1") (pin "23") (pinfunction "NC_23") (pintype "passive"))
    )
    (net (code "89") (name "unconnected-(U2-NC-Pad23)") (class "Default")
      (node (ref "U2") (pin "23") (pinfunction "NC_23") (pintype "passive"))
    )
  )
)
